# 1-Schematic_Power_Supply_Hub_with_INA219.net
KiCad netlist of a schematic drawn in EasyEDA
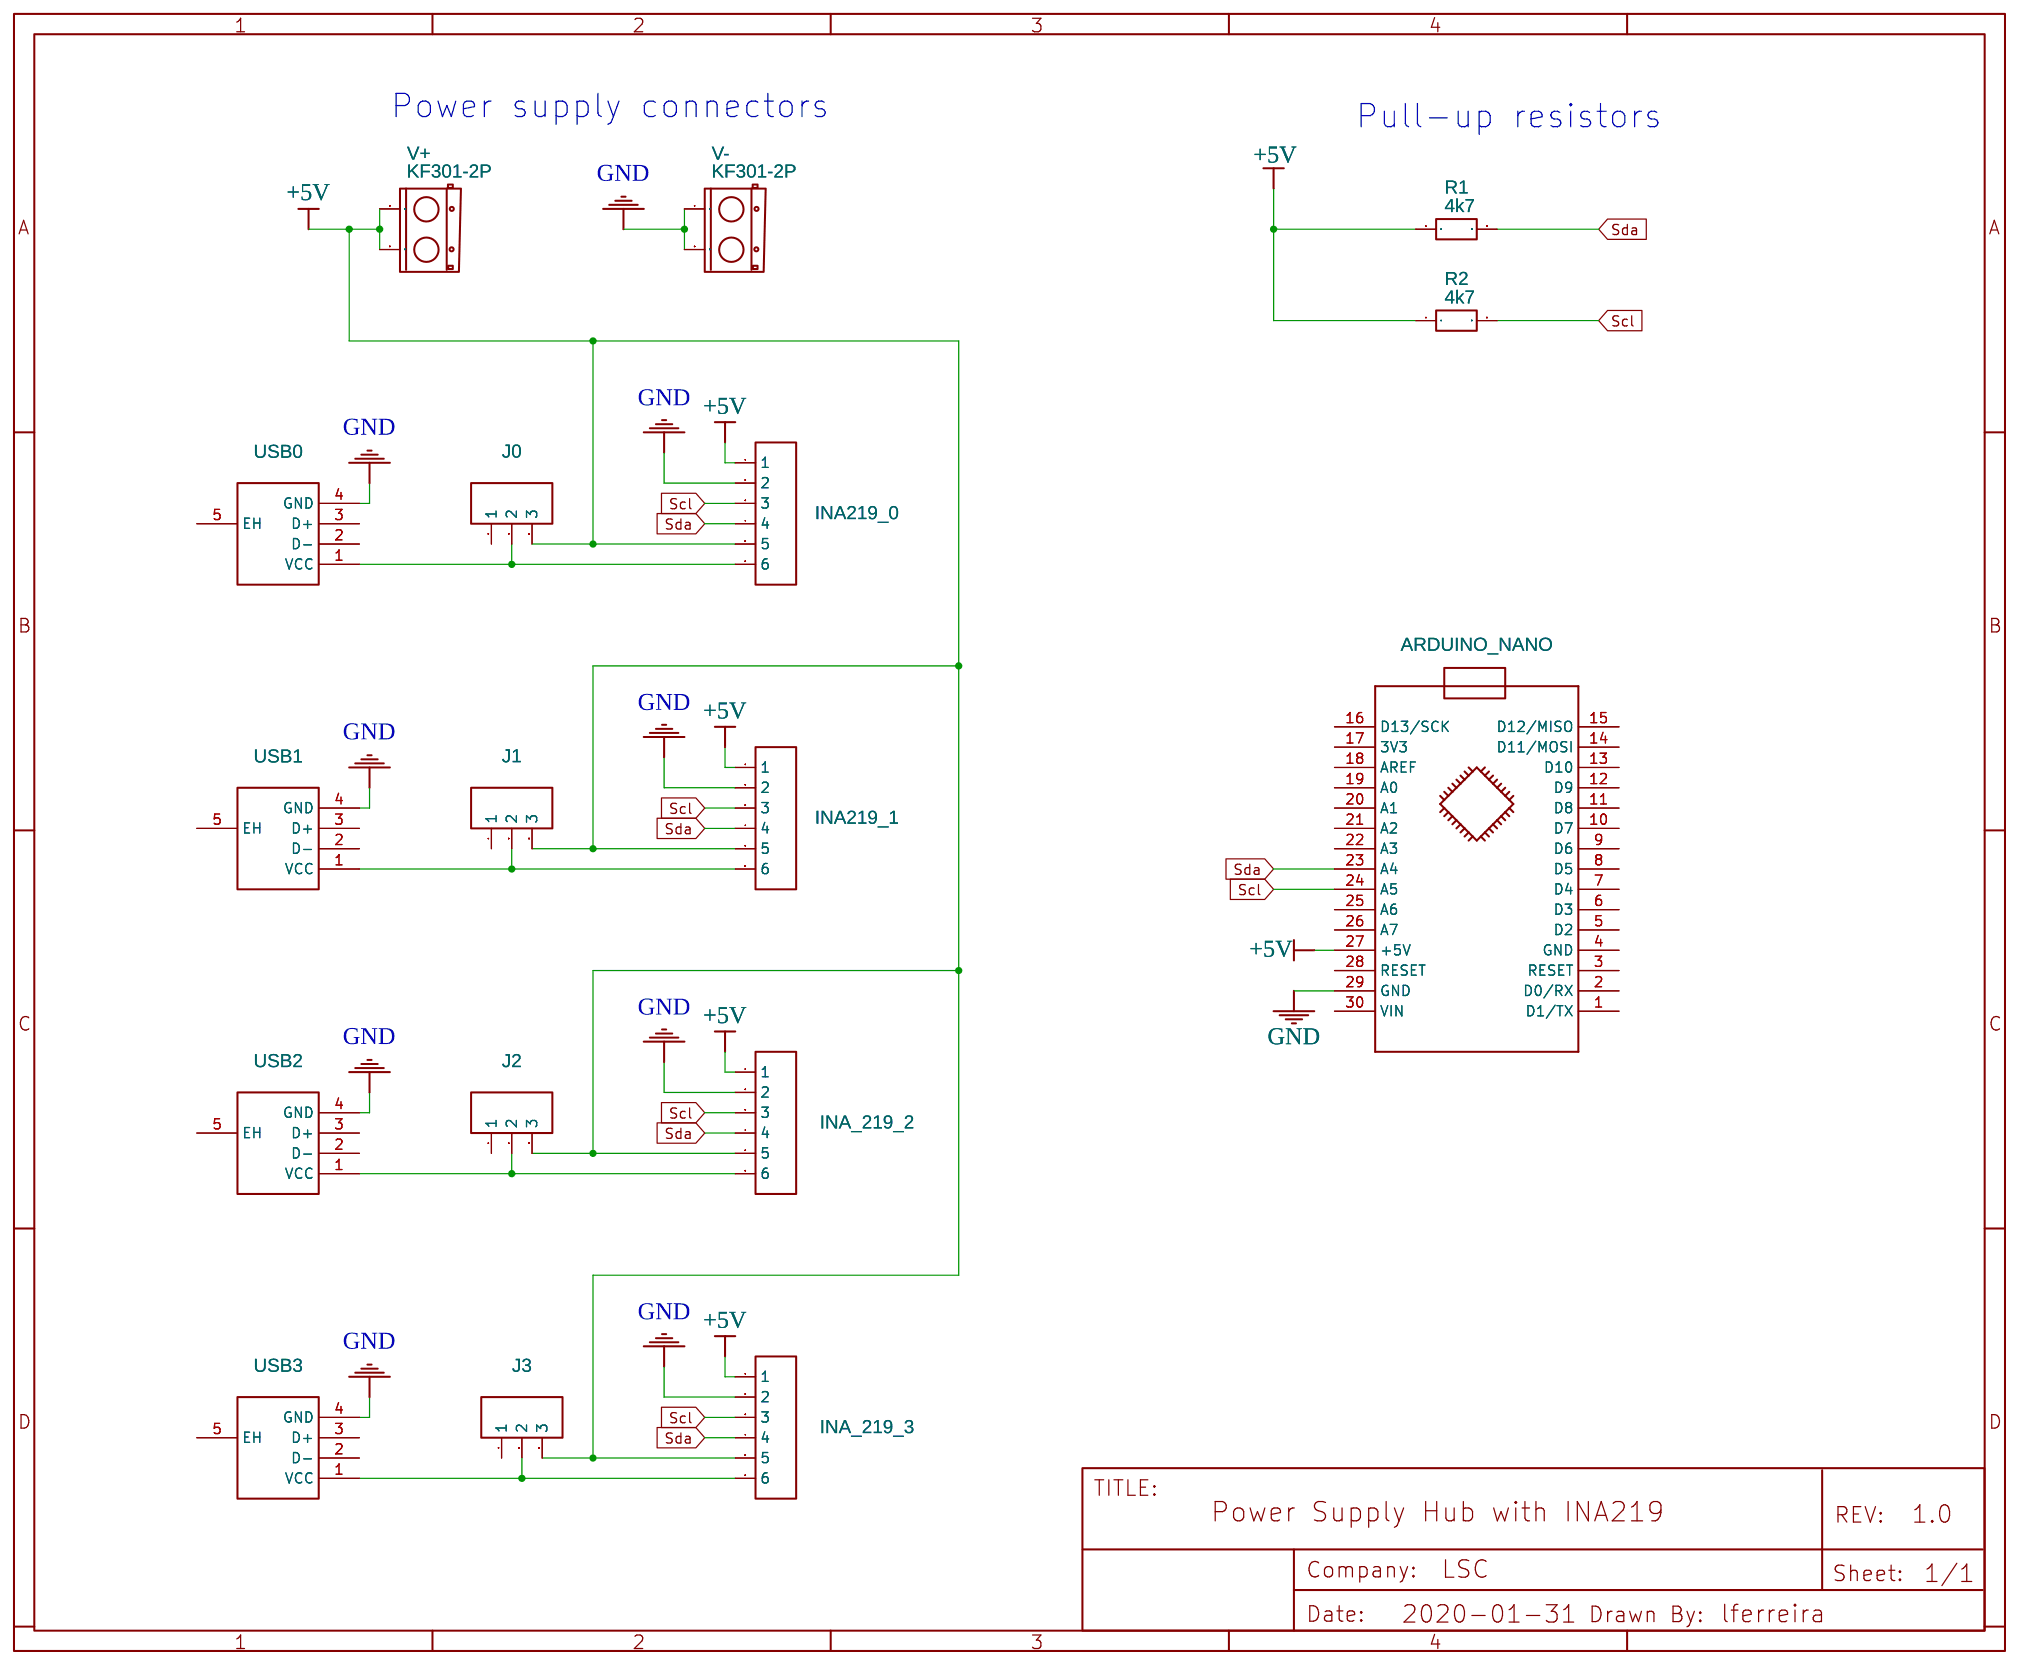
[diagram p0: schematic sheet]

(export (version "E")
  (design (tool "Eeschema 10.0.6"))
  (components
    (comp (ref "INA219_0")
      (value "Header-Female-2.54_1x6")
      (fields
        (field (name "BOM_Manufacturer Part") "Female header 1*6p")
        (field (name "BOM_Supplier Part") "C40877")
      )
      (libsource (lib "") (part "Header-Female-2.54_1x6_1"))
    )
    (comp (ref "INA219_1")
      (value "Header-Female-2.54_1x6")
      (fields
        (field (name "BOM_Manufacturer Part") "Female header 1*6p")
        (field (name "BOM_Supplier Part") "C40877")
      )
      (libsource (lib "") (part "Header-Female-2.54_1x6_1"))
    )
    (comp (ref "INA_219_2")
      (value "Header-Female-2.54_1x6")
      (fields
        (field (name "BOM_Manufacturer Part") "Female header 1*6p")
        (field (name "BOM_Supplier Part") "C40877")
      )
      (libsource (lib "") (part "Header-Female-2.54_1x6"))
    )
    (comp (ref "INA_219_3")
      (value "Header-Female-2.54_1x6")
      (fields
        (field (name "BOM_Manufacturer Part") "Female header 1*6p")
        (field (name "BOM_Supplier Part") "C40877")
      )
      (libsource (lib "") (part "Header-Female-2.54_1x6"))
    )
    (comp (ref "J0")
      (value "Header-Male-2.54_1x3")
      (fields
        (field (name "BOM_Manufacturer Part") "Header2.54mm 1*3P")
        (field (name "BOM_Supplier Part") "C49257")
      )
      (libsource (lib "") (part "Header-Male-2.54_1x3"))
    )
    (comp (ref "J1")
      (value "Header-Male-2.54_1x3")
      (fields
        (field (name "BOM_Manufacturer Part") "Header2.54mm 1*3P")
        (field (name "BOM_Supplier Part") "C49257")
      )
      (libsource (lib "") (part "Header-Male-2.54_1x3"))
    )
    (comp (ref "J2")
      (value "Header-Male-2.54_1x3")
      (fields
        (field (name "BOM_Manufacturer Part") "Header2.54mm 1*3P")
        (field (name "BOM_Supplier Part") "C49257")
      )
      (libsource (lib "") (part "Header-Male-2.54_1x3"))
    )
    (comp (ref "J3")
      (value "Header-Male-2.54_1x3")
      (fields
        (field (name "BOM_Manufacturer Part") "Header2.54mm 1*3P")
        (field (name "BOM_Supplier Part") "C49257")
      )
      (libsource (lib "") (part "Header-Male-2.54_1x3"))
    )
    (comp (ref "R1") (value "4k7") (libsource (lib "") (part "Res_AXIAL-0.4(1/4W)_EU")))
    (comp (ref "R2") (value "4k7") (libsource (lib "") (part "Res_AXIAL-0.4(1/4W)_EU")))
    (comp (ref "U1") (value "ARDUINO_NANO") (libsource (lib "") (part "ARDUINO_NANO")))
    (comp (ref "USB0")
      (value "FUS230-FDBW1K")
      (fields (field (name "BOM_Supplier Part") "C456331"))
      (libsource (lib "") (part "FUS230-FDBW1K"))
    )
    (comp (ref "USB1")
      (value "FUS230-FDBW1K")
      (fields (field (name "BOM_Supplier Part") "C456331"))
      (libsource (lib "") (part "FUS230-FDBW1K"))
    )
    (comp (ref "USB2")
      (value "FUS230-FDBW1K")
      (fields (field (name "BOM_Supplier Part") "C456331"))
      (libsource (lib "") (part "FUS230-FDBW1K"))
    )
    (comp (ref "USB3")
      (value "FUS230-FDBW1K")
      (fields (field (name "BOM_Supplier Part") "C456331"))
      (libsource (lib "") (part "FUS230-FDBW1K"))
    )
    (comp (ref "V+")
      (value "KF301-2P")
      (fields (field (name "BOM_Manufacturer Part") "KF301"))
      (libsource (lib "") (part "KF301-2P_1"))
    )
    (comp (ref "V-")
      (value "KF301-2P")
      (fields (field (name "BOM_Manufacturer Part") "KF301"))
      (libsource (lib "") (part "KF301-2P"))
    )
  )
  (nets
    (net (code "1") (name "+5V") (class "Default")
      (node (ref "INA219_0") (pin "1") (pinfunction "1_1") (pintype "input"))
      (node (ref "INA219_0") (pin "5") (pinfunction "5_5") (pintype "input"))
      (node (ref "INA219_1") (pin "1") (pinfunction "1_1") (pintype "input"))
      (node (ref "INA219_1") (pin "5") (pinfunction "5_5") (pintype "input"))
      (node (ref "INA_219_2") (pin "1") (pinfunction "1_1") (pintype "input"))
      (node (ref "INA_219_2") (pin "5") (pinfunction "5_5") (pintype "input"))
      (node (ref "INA_219_3") (pin "1") (pinfunction "1_1") (pintype "input"))
      (node (ref "INA_219_3") (pin "5") (pinfunction "5_5") (pintype "input"))
      (node (ref "J0") (pin "3") (pinfunction "3_3") (pintype "input"))
      (node (ref "J1") (pin "3") (pinfunction "3_3") (pintype "input"))
      (node (ref "J2") (pin "3") (pinfunction "3_3") (pintype "input"))
      (node (ref "J3") (pin "3") (pinfunction "3_3") (pintype "input"))
      (node (ref "R1") (pin "1") (pinfunction "1_1") (pintype "unspecified"))
      (node (ref "R2") (pin "1") (pinfunction "1_1") (pintype "unspecified"))
      (node (ref "U1") (pin "27") (pinfunction "+5V_27") (pintype "unspecified"))
      (node (ref "V+") (pin "1") (pinfunction "1_1") (pintype "unspecified"))
      (node (ref "V+") (pin "2") (pinfunction "2_2") (pintype "unspecified"))
    )
    (net (code "2") (name "GND") (class "Default")
      (node (ref "INA219_0") (pin "2") (pinfunction "2_2") (pintype "input"))
      (node (ref "INA219_1") (pin "2") (pinfunction "2_2") (pintype "input"))
      (node (ref "INA_219_2") (pin "2") (pinfunction "2_2") (pintype "input"))
      (node (ref "INA_219_3") (pin "2") (pinfunction "2_2") (pintype "input"))
      (node (ref "U1") (pin "29") (pinfunction "GND_29") (pintype "unspecified"))
      (node (ref "USB0") (pin "4") (pinfunction "GND_4") (pintype "unspecified"))
      (node (ref "USB1") (pin "4") (pinfunction "GND_4") (pintype "unspecified"))
      (node (ref "USB2") (pin "4") (pinfunction "GND_4") (pintype "unspecified"))
      (node (ref "USB3") (pin "4") (pinfunction "GND_4") (pintype "unspecified"))
      (node (ref "V-") (pin "1") (pinfunction "1_1") (pintype "unspecified"))
      (node (ref "V-") (pin "2") (pinfunction "2_2") (pintype "unspecified"))
    )
    (net (code "3") (name "Net-(USB0-VCC)") (class "Default")
      (node (ref "INA219_0") (pin "6") (pinfunction "6_6") (pintype "input"))
      (node (ref "J0") (pin "2") (pinfunction "2_2") (pintype "input"))
      (node (ref "USB0") (pin "1") (pinfunction "VCC_1") (pintype "unspecified"))
    )
    (net (code "4") (name "Net-(USB1-VCC)") (class "Default")
      (node (ref "INA219_1") (pin "6") (pinfunction "6_6") (pintype "input"))
      (node (ref "J1") (pin "2") (pinfunction "2_2") (pintype "input"))
      (node (ref "USB1") (pin "1") (pinfunction "VCC_1") (pintype "unspecified"))
    )
    (net (code "5") (name "Net-(USB2-VCC)") (class "Default")
      (node (ref "INA_219_2") (pin "6") (pinfunction "6_6") (pintype "input"))
      (node (ref "J2") (pin "2") (pinfunction "2_2") (pintype "input"))
      (node (ref "USB2") (pin "1") (pinfunction "VCC_1") (pintype "unspecified"))
    )
    (net (code "6") (name "Net-(USB3-VCC)") (class "Default")
      (node (ref "INA_219_3") (pin "6") (pinfunction "6_6") (pintype "input"))
      (node (ref "J3") (pin "2") (pinfunction "2_2") (pintype "input"))
      (node (ref "USB3") (pin "1") (pinfunction "VCC_1") (pintype "unspecified"))
    )
    (net (code "7") (name "Scl") (class "Default")
      (node (ref "INA219_0") (pin "3") (pinfunction "3_3") (pintype "input"))
      (node (ref "INA219_1") (pin "3") (pinfunction "3_3") (pintype "input"))
      (node (ref "INA_219_2") (pin "3") (pinfunction "3_3") (pintype "input"))
      (node (ref "INA_219_3") (pin "3") (pinfunction "3_3") (pintype "input"))
      (node (ref "R2") (pin "2") (pinfunction "2_2") (pintype "unspecified"))
      (node (ref "U1") (pin "24") (pinfunction "A5_24") (pintype "unspecified"))
    )
    (net (code "8") (name "Sda") (class "Default")
      (node (ref "INA219_0") (pin "4") (pinfunction "4_4") (pintype "input"))
      (node (ref "INA219_1") (pin "4") (pinfunction "4_4") (pintype "input"))
      (node (ref "INA_219_2") (pin "4") (pinfunction "4_4") (pintype "input"))
      (node (ref "INA_219_3") (pin "4") (pinfunction "4_4") (pintype "input"))
      (node (ref "R1") (pin "2") (pinfunction "2_2") (pintype "unspecified"))
      (node (ref "U1") (pin "23") (pinfunction "A4_23") (pintype "unspecified"))
    )
    (net (code "9") (name "unconnected-(J0-Pad1)") (class "Default")
      (node (ref "J0") (pin "1") (pinfunction "1_1") (pintype "input"))
    )
    (net (code "10") (name "unconnected-(J1-Pad1)") (class "Default")
      (node (ref "J1") (pin "1") (pinfunction "1_1") (pintype "input"))
    )
    (net (code "11") (name "unconnected-(J2-Pad1)") (class "Default")
      (node (ref "J2") (pin "1") (pinfunction "1_1") (pintype "input"))
    )
    (net (code "12") (name "unconnected-(J3-Pad1)") (class "Default")
      (node (ref "J3") (pin "1") (pinfunction "1_1") (pintype "input"))
    )
    (net (code "13") (name "unconnected-(U1-3V3-Pad17)") (class "Default")
      (node (ref "U1") (pin "17") (pinfunction "3V3_17") (pintype "unspecified"))
    )
    (net (code "14") (name "unconnected-(U1-A0-Pad19)") (class "Default")
      (node (ref "U1") (pin "19") (pinfunction "A0_19") (pintype "unspecified"))
    )
    (net (code "15") (name "unconnected-(U1-A1-Pad20)") (class "Default")
      (node (ref "U1") (pin "20") (pinfunction "A1_20") (pintype "unspecified"))
    )
    (net (code "16") (name "unconnected-(U1-A2-Pad21)") (class "Default")
      (node (ref "U1") (pin "21") (pinfunction "A2_21") (pintype "unspecified"))
    )
    (net (code "17") (name "unconnected-(U1-A3-Pad22)") (class "Default")
      (node (ref "U1") (pin "22") (pinfunction "A3_22") (pintype "unspecified"))
    )
    (net (code "18") (name "unconnected-(U1-A6-Pad25)") (class "Default")
      (node (ref "U1") (pin "25") (pinfunction "A6_25") (pintype "unspecified"))
    )
    (net (code "19") (name "unconnected-(U1-A7-Pad26)") (class "Default")
      (node (ref "U1") (pin "26") (pinfunction "A7_26") (pintype "unspecified"))
    )
    (net (code "20") (name "unconnected-(U1-AREF-Pad18)") (class "Default")
      (node (ref "U1") (pin "18") (pinfunction "AREF_18") (pintype "unspecified"))
    )
    (net (code "21") (name "unconnected-(U1-D0{slash}RX-Pad2)") (class "Default")
      (node (ref "U1") (pin "2") (pinfunction "D0/RX_2") (pintype "unspecified"))
    )
    (net (code "22") (name "unconnected-(U1-D1{slash}TX-Pad1)") (class "Default")
      (node (ref "U1") (pin "1") (pinfunction "D1/TX_1") (pintype "unspecified"))
    )
    (net (code "23") (name "unconnected-(U1-D2-Pad5)") (class "Default")
      (node (ref "U1") (pin "5") (pinfunction "D2_5") (pintype "unspecified"))
    )
    (net (code "24") (name "unconnected-(U1-D3-Pad6)") (class "Default")
      (node (ref "U1") (pin "6") (pinfunction "D3_6") (pintype "unspecified"))
    )
    (net (code "25") (name "unconnected-(U1-D4-Pad7)") (class "Default")
      (node (ref "U1") (pin "7") (pinfunction "D4_7") (pintype "unspecified"))
    )
    (net (code "26") (name "unconnected-(U1-D5-Pad8)") (class "Default")
      (node (ref "U1") (pin "8") (pinfunction "D5_8") (pintype "unspecified"))
    )
    (net (code "27") (name "unconnected-(U1-D6-Pad9)") (class "Default")
      (node (ref "U1") (pin "9") (pinfunction "D6_9") (pintype "unspecified"))
    )
    (net (code "28") (name "unconnected-(U1-D7-Pad10)") (class "Default")
      (node (ref "U1") (pin "10") (pinfunction "D7_10") (pintype "unspecified"))
    )
    (net (code "29") (name "unconnected-(U1-D8-Pad11)") (class "Default")
      (node (ref "U1") (pin "11") (pinfunction "D8_11") (pintype "unspecified"))
    )
    (net (code "30") (name "unconnected-(U1-D9-Pad12)") (class "Default")
      (node (ref "U1") (pin "12") (pinfunction "D9_12") (pintype "unspecified"))
    )
    (net (code "31") (name "unconnected-(U1-D10-Pad13)") (class "Default")
      (node (ref "U1") (pin "13") (pinfunction "D10_13") (pintype "unspecified"))
    )
    (net (code "32") (name "unconnected-(U1-D11{slash}MOSI-Pad14)") (class "Default")
      (node (ref "U1") (pin "14") (pinfunction "D11/MOSI_14") (pintype "unspecified"))
    )
    (net (code "33") (name "unconnected-(U1-D12{slash}MISO-Pad15)") (class "Default")
      (node (ref "U1") (pin "15") (pinfunction "D12/MISO_15") (pintype "unspecified"))
    )
    (net (code "34") (name "unconnected-(U1-D13{slash}SCK-Pad16)") (class "Default")
      (node (ref "U1") (pin "16") (pinfunction "D13/SCK_16") (pintype "unspecified"))
    )
    (net (code "35") (name "unconnected-(U1-GND-Pad4)") (class "Default")
      (node (ref "U1") (pin "4") (pinfunction "GND_4") (pintype "unspecified"))
    )
    (net (code "36") (name "unconnected-(U1-RESET-Pad3)") (class "Default")
      (node (ref "U1") (pin "3") (pinfunction "RESET_3") (pintype "unspecified"))
    )
    (net (code "37") (name "unconnected-(U1-RESET-Pad28)") (class "Default")
      (node (ref "U1") (pin "28") (pinfunction "RESET_28") (pintype "unspecified"))
    )
    (net (code "38") (name "unconnected-(U1-VIN-Pad30)") (class "Default")
      (node (ref "U1") (pin "30") (pinfunction "VIN_30") (pintype "unspecified"))
    )
    (net (code "39") (name "unconnected-(USB0-D+-Pad3)") (class "Default")
      (node (ref "USB0") (pin "3") (pinfunction "D+_3") (pintype "unspecified"))
    )
    (net (code "40") (name "unconnected-(USB0-D--Pad2)") (class "Default")
      (node (ref "USB0") (pin "2") (pinfunction "D-_2") (pintype "unspecified"))
    )
    (net (code "41") (name "unconnected-(USB0-EH-Pad5)") (class "Default")
      (node (ref "USB0") (pin "5") (pinfunction "EH_5") (pintype "unspecified"))
    )
    (net (code "42") (name "unconnected-(USB1-D+-Pad3)") (class "Default")
      (node (ref "USB1") (pin "3") (pinfunction "D+_3") (pintype "unspecified"))
    )
    (net (code "43") (name "unconnected-(USB1-D--Pad2)") (class "Default")
      (node (ref "USB1") (pin "2") (pinfunction "D-_2") (pintype "unspecified"))
    )
    (net (code "44") (name "unconnected-(USB1-EH-Pad5)") (class "Default")
      (node (ref "USB1") (pin "5") (pinfunction "EH_5") (pintype "unspecified"))
    )
    (net (code "45") (name "unconnected-(USB2-D+-Pad3)") (class "Default")
      (node (ref "USB2") (pin "3") (pinfunction "D+_3") (pintype "unspecified"))
    )
    (net (code "46") (name "unconnected-(USB2-D--Pad2)") (class "Default")
      (node (ref "USB2") (pin "2") (pinfunction "D-_2") (pintype "unspecified"))
    )
    (net (code "47") (name "unconnected-(USB2-EH-Pad5)") (class "Default")
      (node (ref "USB2") (pin "5") (pinfunction "EH_5") (pintype "unspecified"))
    )
    (net (code "48") (name "unconnected-(USB3-D+-Pad3)") (class "Default")
      (node (ref "USB3") (pin "3") (pinfunction "D+_3") (pintype "unspecified"))
    )
    (net (code "49") (name "unconnected-(USB3-D--Pad2)") (class "Default")
      (node (ref "USB3") (pin "2") (pinfunction "D-_2") (pintype "unspecified"))
    )
    (net (code "50") (name "unconnected-(USB3-EH-Pad5)") (class "Default")
      (node (ref "USB3") (pin "5") (pinfunction "EH_5") (pintype "unspecified"))
    )
  )
)
